# Esquem_tico.net
KiCad netlist of a schematic drawn in Altium Designer
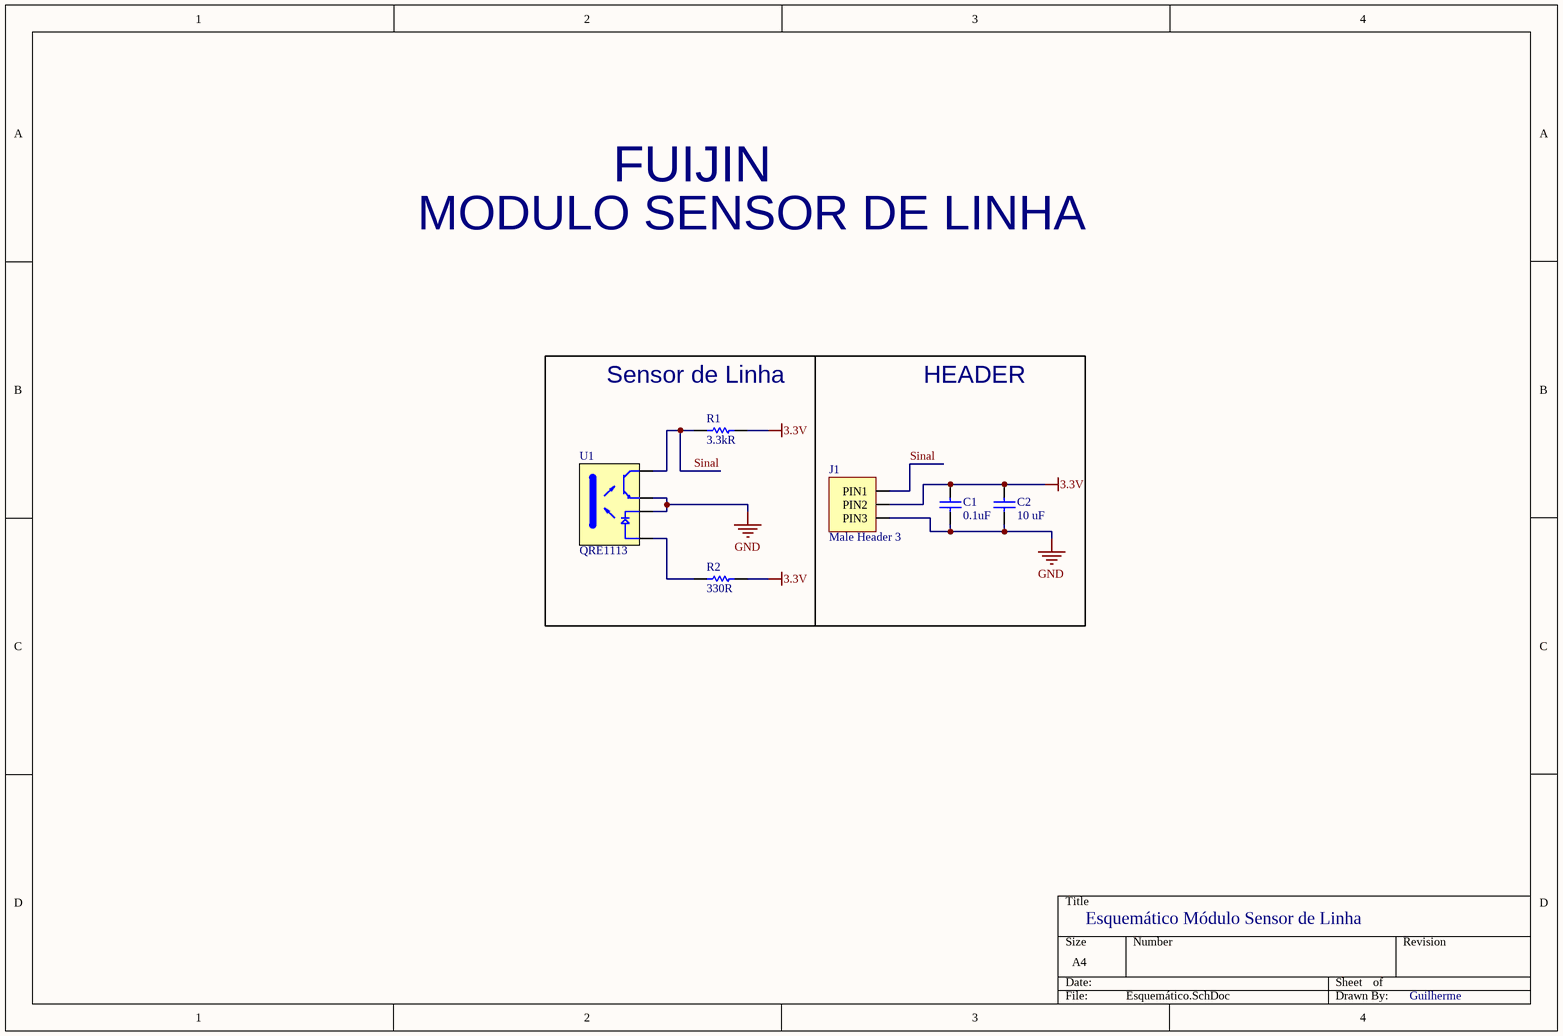
[diagram p0: Esquemático.SchDoc]

(export (version "E")
  (design (tool "Eeschema 10.0.6"))
  (components
    (comp (ref "C1")
      (value "0.1uF")
      (footprint "CAPC1005X55N")
      (description "CAP CER 0.1uF 16V X5R 0402")
      (fields
        (field (name "MANUFACTURER") "Murata")
        (field (name "PART NUMBER") "GRM155R61C104KA88D")
        (field (name "LIBRARY CONTROL - PERSON THAT CHECKED FOOTPRINT") "Guilherme")
        (field (name "LIBRARY CONTROL - PERSON THAT CHECKED SCHEMATIC") "Guilherme")
        (field (name "LIBRARY CONTROL - PERSON THAT DID THE LAST UPDATE FOOTPRINT") "Guilherme")
        (field (name "LIBRARY CONTROL - PERSON THAT DID THE LAST UPDATE SCHEMATIC") "Guilherme")
      )
      (libsource (lib "Uai!Tecas") (part "GRM155R61C104KA88D"))
    )
    (comp (ref "C2")
      (value "10 uF")
      (footprint "C0603")
      (description "CAP CER 10uF 16V X5R 0603")
      (fields
        (field (name "MANUFACTURER") "MURATA ELECTRONICS")
        (field (name "PART NUMBER") "GRM188R61C106MA73D")
        (field (name "LIBRARY CONTROL - CHECKED SCHEMATIC") "Guilherme")
        (field (name "LIBRARY CONTROL - PERSON THAT CHECKED SCHEMATIC") "Guilherme")
        (field (name "LIBRARY CONTROL - PERSON THAT DID THE LAST UPDATE FOOTPRINT") "Raquel")
        (field (name "LIBRARY CONTROL - PERSON THAT DID THE LAST UPDATE SCHEMATIC") "Marcos")
      )
      (libsource (lib "Uai!Tecas") (part "GRM188R61C106MA73D"))
    )
    (comp (ref "J1")
      (value "Male Header 3")
      (footprint "MALE HEADER 3")
      (fields
        (field (name "LIBRARY CONTROL - PERSON THAT DID THE LAST UPDATE SCHEMATIC") "Guilherme")
        (field (name "LIBRARY CONTROL - PERSONT THAT DID THE LAST UPDATE FOOTPRINT") "Guilherme")
      )
      (libsource (lib "Uai!Tecas") (part "Male Header 3"))
    )
    (comp (ref "R1")
      (value "3.3kR")
      (footprint "RESISTOR_0603")
      (description "RES SMD 3.3K OHM 1% 1/10W 0603")
      (fields
        (field (name "MANUFACTURER") "TE Connectivity / Holsworthy")
        (field (name "PART NUMBER") "CRGCQ0603F3K3")
        (field (name "LIBRARY CONTROL - PERSON THAT CHECKED FOOTPRINT") "Nikaum")
        (field (name "LIBRARY CONTROL - PERSON THAT CHECKED SCHEMATIC") "Guilherme")
        (field (name "LIBRARY CONTROL - PERSON THAT DID THE LAST UPDATE FOOTPRINT") "Dalarme")
        (field (name "LIBRARY CONTROL - PERSON THAT DID THE LAST UPDATE SCHEMATIC") "Dalarme")
      )
      (libsource (lib "Uai!Tecas") (part "CRGCQ0603F3K3"))
    )
    (comp (ref "R2")
      (value "330R")
      (footprint "RESISTOR_0603")
      (description "RES SMD 330 OHM 5% 1/10W 0603")
      (fields
        (field (name "MANUFACTURER") "Yageo")
        (field (name "PART NUMBER") "RC0603JR-07330RL")
        (field (name "LIBRARY CONTROL - PERSON THAT CHECKED SCHEMATIC") "Guilherme")
        (field (name "LIBRARY CONTROL - PERSON THAT DID THE LAST UPDATE FOOTPRINT") "Dalarme")
        (field (name "LIBRARY CONTROL - PERSON THAT DID THE LAST UPDATE SCHEMATIC") "Dalarme")
      )
      (libsource (lib "Uai!Tecas") (part "RC0603JR-07330RL"))
    )
    (comp (ref "U1")
      (value "QRE1113")
      (footprint "QRE1113")
      (description "PHOTOTRANSISTORQRE1113 - 1CH - Tube")
      (fields
        (field (name "MANUFACTURER") "ON Semiconductor")
        (field (name "LIBRARY CONTROL - PERSON THAT CHECKED FOOTPRINT") "Nikaum")
        (field (name "LIBRARY CONTROL - PERSON THAT CHECKED SCHEMATIC") "Nikaum")
        (field (name "LIBRARY CONTROL - PERSON THAT DID THE LAST UPDATE IN FOOTPRINT") "Nikaum")
        (field (name "LIBRARY CONTROL - PERSON THAT DID THE LAST UPDATE IN SCHEMATIC") "Nikaum")
      )
      (libsource (lib "Uai!Tecas") (part "QRE1113"))
    )
  )
  (nets
    (net (code "1") (name "/Sinal") (class "Default")
      (node (ref "J1") (pin "PIN1") (pinfunction "PIN1_PIN1") (pintype "passive"))
      (node (ref "R1") (pin "1") (pinfunction "1_1") (pintype "passive"))
      (node (ref "U1") (pin "CT") (pinfunction "CT_CT") (pintype "passive"))
    )
    (net (code "2") (name "3.3V") (class "Default")
      (node (ref "C1") (pin "2") (pinfunction "2_2") (pintype "passive"))
      (node (ref "C2") (pin "2") (pinfunction "2_2") (pintype "passive"))
      (node (ref "J1") (pin "PIN2") (pinfunction "PIN2_PIN2") (pintype "passive"))
      (node (ref "R1") (pin "2") (pinfunction "2_2") (pintype "passive"))
      (node (ref "R2") (pin "2") (pinfunction "2_2") (pintype "passive"))
    )
    (net (code "3") (name "GND") (class "Default")
      (node (ref "C1") (pin "1") (pinfunction "1_1") (pintype "passive"))
      (node (ref "C2") (pin "1") (pinfunction "1_1") (pintype "passive"))
      (node (ref "J1") (pin "PIN3") (pinfunction "PIN3_PIN3") (pintype "passive"))
      (node (ref "U1") (pin "C") (pinfunction "C_C") (pintype "passive"))
      (node (ref "U1") (pin "ET") (pinfunction "ET_ET") (pintype "passive"))
    )
    (net (code "4") (name "Net-(R2-Pad1)") (class "Default")
      (node (ref "R2") (pin "1") (pinfunction "1_1") (pintype "passive"))
      (node (ref "U1") (pin "A") (pinfunction "A_A") (pintype "passive"))
    )
  )
)
